# Sensor.net
KiCad netlist of a schematic drawn in Altium Designer
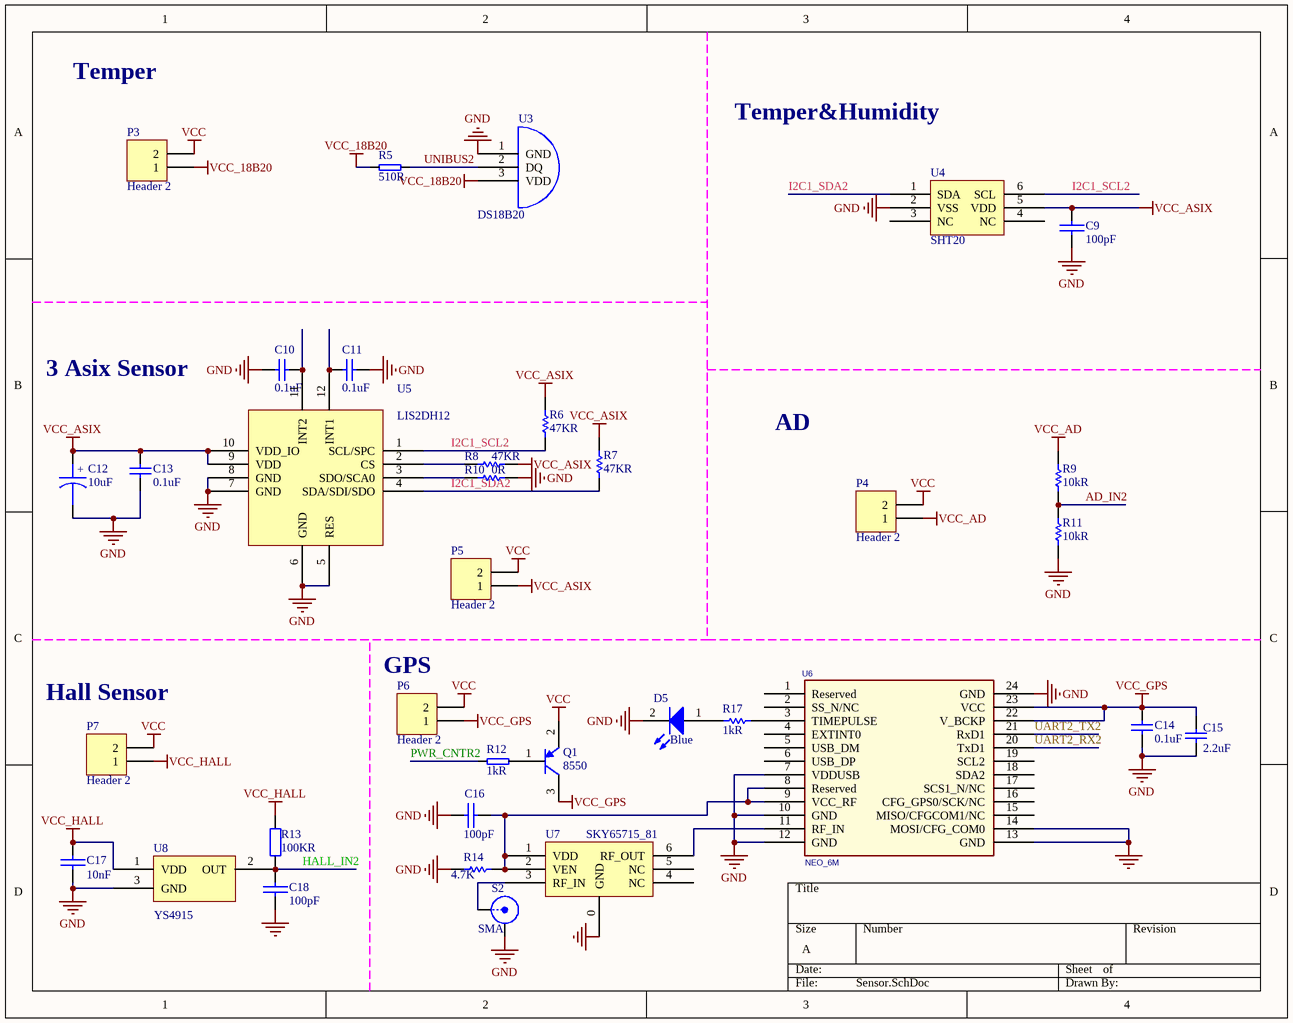
[diagram p0: Sensor.SchDoc]

(export (version "E")
  (design (tool "Eeschema 10.0.6"))
  (components
    (comp (ref "C9")
      (value "100pF")
      (footprint "0603RF")
      (description "Capacitor")
      (libsource (lib "") (part "CAP_1"))
    )
    (comp (ref "C10")
      (value "0.1uF")
      (footprint "0603RF")
      (description "Capacitor (Semiconductor SIM Model)")
      (fields (field (name "PUBLISHER") "Altium Limited"))
      (libsource (lib "Miscellaneous Devices") (part "Cap Semi"))
    )
    (comp (ref "C11")
      (value "0.1uF")
      (footprint "0603RF")
      (description "Capacitor (Semiconductor SIM Model)")
      (fields (field (name "PUBLISHER") "Altium Limited"))
      (libsource (lib "Miscellaneous Devices") (part "Cap Semi"))
    )
    (comp (ref "C12")
      (value "10uF")
      (footprint "0805")
      (description "Capacitor")
      (libsource (lib "*") (part "CAPACITOR POL"))
    )
    (comp (ref "C13")
      (value "0.1uF")
      (footprint "0603RF")
      (description "Capacitor (Semiconductor SIM Model)")
      (fields (field (name "PUBLISHER") "Altium Limited"))
      (libsource (lib "Miscellaneous Devices") (part "Cap Semi"))
    )
    (comp (ref "C14")
      (value "0.1uF")
      (footprint "0603RF")
      (description "Capacitor (Semiconductor SIM Model)")
      (fields (field (name "PUBLISHER") "Altium Limited"))
      (libsource (lib "Miscellaneous Devices") (part "Cap Semi"))
    )
    (comp (ref "C15")
      (value "2.2uF")
      (footprint "0603RF")
      (description "Capacitor (Semiconductor SIM Model)")
      (fields (field (name "PUBLISHER") "Altium Limited"))
      (libsource (lib "Miscellaneous Devices") (part "Cap Semi"))
    )
    (comp (ref "C16")
      (value "100pF")
      (footprint "0603RF")
      (description "Capacitor,100pF/50V,10%,C0603")
      (libsource (lib "Jude") (part "100pF/50V,10%,C0603"))
    )
    (comp (ref "C17")
      (value "10nF")
      (footprint "0603RF")
      (description "Capacitor")
      (libsource (lib "*") (part "CAP"))
    )
    (comp (ref "C18")
      (value "100pF")
      (footprint "0603RF")
      (description "Capacitor")
      (libsource (lib "*") (part "CAP"))
    )
    (comp (ref "D5")
      (value "Blue")
      (footprint "LED0603")
      (description "Typical RED, GREEN, YELLOW, AMBER GaAs LED")
      (fields (field (name "PUBLISHER") "Altium Limited"))
      (libsource (lib "*") (part "LED2"))
    )
    (comp (ref "P3")
      (value "Header 2")
      (footprint "HDR1X2")
      (description "Header, 2-Pin")
      (fields (field (name "PUBLISHER") "Altium Limited"))
      (libsource (lib "Miscellaneous Connectors") (part "Header 2"))
    )
    (comp (ref "P4")
      (value "Header 2")
      (footprint "HDR1X2")
      (description "Header, 2-Pin")
      (fields (field (name "PUBLISHER") "Altium Limited"))
      (libsource (lib "Miscellaneous Connectors") (part "Header 2"))
    )
    (comp (ref "P5")
      (value "Header 2")
      (footprint "HDR1X2")
      (description "Header, 2-Pin")
      (fields (field (name "PUBLISHER") "Altium Limited"))
      (libsource (lib "Miscellaneous Connectors") (part "Header 2"))
    )
    (comp (ref "P6")
      (value "Header 2")
      (footprint "HDR1X2")
      (description "Header, 2-Pin")
      (fields (field (name "PUBLISHER") "Altium Limited"))
      (libsource (lib "Miscellaneous Connectors") (part "Header 2"))
    )
    (comp (ref "P7")
      (value "Header 2")
      (footprint "HDR1X2")
      (description "Header, 2-Pin")
      (fields (field (name "PUBLISHER") "Altium Limited"))
      (libsource (lib "Miscellaneous Connectors") (part "Header 2"))
    )
    (comp (ref "Q1")
      (value "8550")
      (footprint "SO-G3/Z3.3")
      (description "PNP三极管")
      (libsource (lib "MySCHLIB") (part "8550"))
    )
    (comp (ref "R5") (value "510R") (footprint "0603RF") (libsource (lib "*") (part "R")))
    (comp (ref "R6")
      (value "47KR")
      (footprint "0603RF")
      (description "Semiconductor Resistor")
      (fields (field (name "PUBLISHER") "Altium Limited"))
      (libsource (lib "Miscellaneous Devices") (part "Res Semi"))
    )
    (comp (ref "R7")
      (value "47KR")
      (footprint "0603RF")
      (description "Semiconductor Resistor")
      (fields (field (name "PUBLISHER") "Altium Limited"))
      (libsource (lib "Miscellaneous Devices") (part "Res Semi"))
    )
    (comp (ref "R8")
      (value "47KR")
      (footprint "0603RF")
      (description "Semiconductor Resistor")
      (fields (field (name "PUBLISHER") "Altium Limited"))
      (libsource (lib "Miscellaneous Devices") (part "Res Semi"))
    )
    (comp (ref "R9")
      (value "10kR")
      (footprint "0603RF")
      (description "Semiconductor Resistor")
      (fields (field (name "PUBLISHER") "Altium Limited"))
      (libsource (lib "Miscellaneous Devices") (part "Res Semi"))
    )
    (comp (ref "R10")
      (value "0R")
      (footprint "0603RF")
      (description "Semiconductor Resistor")
      (fields (field (name "PUBLISHER") "Altium Limited"))
      (libsource (lib "Miscellaneous Devices") (part "Res Semi"))
    )
    (comp (ref "R11")
      (value "10kR")
      (footprint "0603RF")
      (description "Semiconductor Resistor")
      (fields (field (name "PUBLISHER") "Altium Limited"))
      (libsource (lib "Miscellaneous Devices") (part "Res Semi"))
    )
    (comp (ref "R12") (value "1kR") (footprint "0603RF") (libsource (lib "*") (part "R")))
    (comp (ref "R13")
      (value "100KR")
      (footprint "0603RF")
      (description "Resistor")
      (fields (field (name "PUBLISHER") "Altium Limited"))
      (libsource (lib "Miscellaneous Devices") (part "Res2"))
    )
    (comp (ref "R14") (value "4.7K") (footprint "0603RF") (libsource (lib "Jude") (part "0R,5%,R1206")))
    (comp (ref "R17")
      (value "1kR")
      (footprint "0603RF")
      (description "Semiconductor Resistor")
      (fields (field (name "PUBLISHER") "Altium Limited"))
      (libsource (lib "Miscellaneous Devices") (part "Res Semi"))
    )
    (comp (ref "S2")
      (value "SMA")
      (footprint "SMA")
      (description "SMB Straight Connector")
      (fields (field (name "PUBLISHER") "Altium Limited"))
      (libsource (lib "Miscellaneous Connectors") (part "SMB"))
    )
    (comp (ref "U3")
      (value "DS18B20")
      (footprint "LC-TO-92(TO-92-3)")
      (libsource (lib "MySCHLIB") (part "DS18B20"))
    )
    (comp (ref "U4") (value "SHT20") (footprint "QFN6") (libsource (lib "MySCHLIB") (part "SHT20")))
    (comp (ref "U5") (value "LIS2DH12") (footprint "LIS2DH12") (libsource (lib "MySCHLIB") (part "LIS2DH12")))
    (comp (ref "U6") (value "NEO_6M") (description "GPS模块") (libsource (lib "*") (part "NEO_0")))
    (comp (ref "U7")
      (value "SKY65715_81")
      (footprint "SKY65715")
      (libsource (lib "MySCHLIB") (part "SKY65715"))
    )
    (comp (ref "U8") (value "YS4915") (footprint "SOT-23") (libsource (lib "MySCHLIB") (part "ES248L")))
  )
  (nets
    (net (code "1") (name "/AD_IN2") (class "Default")
      (node (ref "R11") (pin "1") (pinfunction "1_1") (pintype "passive"))
      (node (ref "R9") (pin "2") (pinfunction "2_2") (pintype "passive"))
    )
    (net (code "2") (name "/HALL_IN2") (class "Default")
      (node (ref "C18") (pin "2") (pinfunction "2_2") (pintype "passive"))
      (node (ref "R13") (pin "2") (pinfunction "2_2") (pintype "passive"))
      (node (ref "U8") (pin "2") (pinfunction "OUT_2") (pintype "passive"))
    )
    (net (code "3") (name "/I2C1_SCL2") (class "Default")
      (node (ref "R6") (pin "1") (pinfunction "1_1") (pintype "passive"))
      (node (ref "U4") (pin "6") (pinfunction "SCL_6") (pintype "passive"))
      (node (ref "U5") (pin "1") (pinfunction "SCL/SPC_1") (pintype "passive"))
    )
    (net (code "4") (name "/I2C1_SDA2") (class "Default")
      (node (ref "R7") (pin "1") (pinfunction "1_1") (pintype "passive"))
      (node (ref "U4") (pin "1") (pinfunction "SDA_1") (pintype "passive"))
      (node (ref "U5") (pin "4") (pinfunction "SDA/SDI/SDO_4") (pintype "passive"))
    )
    (net (code "5") (name "/PWR_CNTR2") (class "Default")
      (node (ref "R12") (pin "2") (pinfunction "2_2") (pintype "passive"))
    )
    (net (code "6") (name "/UART2_RX2") (class "Default")
      (node (ref "U6") (pin "20") (pinfunction "TxD1_20") (pintype "passive"))
    )
    (net (code "7") (name "/UART2_TX2") (class "Default")
      (node (ref "U6") (pin "21") (pinfunction "RxD1_21") (pintype "passive"))
    )
    (net (code "8") (name "/UNIBUS2") (class "Default")
      (node (ref "R5") (pin "2") (pinfunction "2_2") (pintype "passive"))
      (node (ref "U3") (pin "2") (pinfunction "DQ_2") (pintype "passive"))
    )
    (net (code "9") (name "GND") (class "Default")
      (node (ref "C10") (pin "2") (pinfunction "2_2") (pintype "passive"))
      (node (ref "C11") (pin "1") (pinfunction "1_1") (pintype "passive"))
      (node (ref "C12") (pin "2") (pinfunction "2_2") (pintype "passive"))
      (node (ref "C13") (pin "1") (pinfunction "1_1") (pintype "passive"))
      (node (ref "C14") (pin "1") (pinfunction "1_1") (pintype "passive"))
      (node (ref "C15") (pin "2") (pinfunction "2_2") (pintype "passive"))
      (node (ref "C16") (pin "1") (pinfunction "1_1") (pintype "passive"))
      (node (ref "C17") (pin "1") (pinfunction "1_1") (pintype "passive"))
      (node (ref "C18") (pin "1") (pinfunction "1_1") (pintype "passive"))
      (node (ref "C9") (pin "1") (pinfunction "1_1") (pintype "passive"))
      (node (ref "D5") (pin "2") (pinfunction "K_2") (pintype "passive"))
      (node (ref "R10") (pin "2") (pinfunction "2_2") (pintype "passive"))
      (node (ref "R11") (pin "2") (pinfunction "2_2") (pintype "passive"))
      (node (ref "R14") (pin "2") (pinfunction "2_2") (pintype "passive"))
      (node (ref "S2") (pin "2") (pinfunction "Y_2") (pintype "passive"))
      (node (ref "U3") (pin "1") (pinfunction "GND_1") (pintype "passive"))
      (node (ref "U4") (pin "2") (pinfunction "VSS_2") (pintype "passive"))
      (node (ref "U5") (pin "5") (pinfunction "RES_5") (pintype "passive"))
      (node (ref "U5") (pin "6") (pinfunction "GND_6") (pintype "passive"))
      (node (ref "U5") (pin "7") (pinfunction "GND_7") (pintype "passive"))
      (node (ref "U5") (pin "8") (pinfunction "GND_8") (pintype "passive"))
      (node (ref "U6") (pin "10") (pinfunction "GND_10") (pintype "passive"))
      (node (ref "U6") (pin "12") (pinfunction "GND_12") (pintype "passive"))
      (node (ref "U6") (pin "13") (pinfunction "GND_13") (pintype "passive"))
      (node (ref "U6") (pin "14") (pinfunction "MOSI/CFG_COM0_14") (pintype "passive"))
      (node (ref "U6") (pin "24") (pinfunction "GND_24") (pintype "passive"))
      (node (ref "U6") (pin "7") (pinfunction "VDDUSB_7") (pintype "passive"))
      (node (ref "U7") (pin "0") (pinfunction "GND_0") (pintype "passive"))
      (node (ref "U8") (pin "3") (pinfunction "GND_3") (pintype "passive"))
    )
    (net (code "10") (name "Net-(D5-A)") (class "Default")
      (node (ref "D5") (pin "1") (pinfunction "A_1") (pintype "passive"))
      (node (ref "R17") (pin "1") (pinfunction "1_1") (pintype "passive"))
    )
    (net (code "11") (name "Net-(Q1-B)") (class "Default")
      (node (ref "Q1") (pin "1") (pinfunction "B_1") (pintype "passive"))
      (node (ref "R12") (pin "1") (pinfunction "1_1") (pintype "passive"))
    )
    (net (code "12") (name "Net-(S2-X)") (class "Default")
      (node (ref "S2") (pin "1") (pinfunction "X_1") (pintype "passive"))
      (node (ref "U7") (pin "3") (pinfunction "RF_IN_3") (pintype "passive"))
    )
    (net (code "13") (name "Net-(U5-CS)") (class "Default")
      (node (ref "R8") (pin "1") (pinfunction "1_1") (pintype "passive"))
      (node (ref "U5") (pin "2") (pinfunction "CS_2") (pintype "passive"))
    )
    (net (code "14") (name "Net-(U5-INT1)") (class "Default")
      (node (ref "C11") (pin "2") (pinfunction "2_2") (pintype "passive"))
      (node (ref "U5") (pin "12") (pinfunction "INT1_12") (pintype "passive"))
    )
    (net (code "15") (name "Net-(U5-INT2)") (class "Default")
      (node (ref "C10") (pin "1") (pinfunction "1_1") (pintype "passive"))
      (node (ref "U5") (pin "11") (pinfunction "INT2_11") (pintype "passive"))
    )
    (net (code "16") (name "Net-(U5-SDO{slash}SCA0)") (class "Default")
      (node (ref "R10") (pin "1") (pinfunction "1_1") (pintype "passive"))
      (node (ref "U5") (pin "3") (pinfunction "SDO/SCA0_3") (pintype "passive"))
    )
    (net (code "17") (name "Net-(U6-RF_IN)") (class "Default")
      (node (ref "U6") (pin "11") (pinfunction "RF_IN_11") (pintype "passive"))
      (node (ref "U7") (pin "6") (pinfunction "RF_OUT_6") (pintype "passive"))
    )
    (net (code "18") (name "Net-(U6-TIMEPULSE)") (class "Default")
      (node (ref "R17") (pin "2") (pinfunction "2_2") (pintype "passive"))
      (node (ref "U6") (pin "3") (pinfunction "TIMEPULSE_3") (pintype "passive"))
    )
    (net (code "19") (name "Net-(U6-VCC_RF)") (class "Default")
      (node (ref "C16") (pin "2") (pinfunction "2_2") (pintype "passive"))
      (node (ref "R14") (pin "1") (pinfunction "1_1") (pintype "passive"))
      (node (ref "U6") (pin "8") (pinfunction "Reserved_8") (pintype "passive"))
      (node (ref "U6") (pin "9") (pinfunction "VCC_RF_9") (pintype "passive"))
      (node (ref "U7") (pin "1") (pinfunction "VDD_1") (pintype "passive"))
      (node (ref "U7") (pin "2") (pinfunction "VEN_2") (pintype "passive"))
    )
    (net (code "20") (name "VCC") (class "Default")
      (node (ref "P3") (pin "2") (pinfunction "2_2") (pintype "passive"))
      (node (ref "P4") (pin "2") (pinfunction "2_2") (pintype "passive"))
      (node (ref "P5") (pin "2") (pinfunction "2_2") (pintype "passive"))
      (node (ref "P6") (pin "2") (pinfunction "2_2") (pintype "passive"))
      (node (ref "P7") (pin "2") (pinfunction "2_2") (pintype "passive"))
      (node (ref "Q1") (pin "2") (pinfunction "E_2") (pintype "passive"))
    )
    (net (code "21") (name "VCC_18B20") (class "Default")
      (node (ref "P3") (pin "1") (pinfunction "1_1") (pintype "passive"))
      (node (ref "R5") (pin "1") (pinfunction "1_1") (pintype "passive"))
      (node (ref "U3") (pin "3") (pinfunction "VDD_3") (pintype "passive"))
    )
    (net (code "22") (name "VCC_AD") (class "Default")
      (node (ref "P4") (pin "1") (pinfunction "1_1") (pintype "passive"))
      (node (ref "R9") (pin "1") (pinfunction "1_1") (pintype "passive"))
    )
    (net (code "23") (name "VCC_ASIX") (class "Default")
      (node (ref "C12") (pin "1") (pinfunction "1_1") (pintype "passive"))
      (node (ref "C13") (pin "2") (pinfunction "2_2") (pintype "passive"))
      (node (ref "C9") (pin "2") (pinfunction "2_2") (pintype "passive"))
      (node (ref "P5") (pin "1") (pinfunction "1_1") (pintype "passive"))
      (node (ref "R6") (pin "2") (pinfunction "2_2") (pintype "passive"))
      (node (ref "R7") (pin "2") (pinfunction "2_2") (pintype "passive"))
      (node (ref "R8") (pin "2") (pinfunction "2_2") (pintype "passive"))
      (node (ref "U4") (pin "5") (pinfunction "VDD_5") (pintype "passive"))
      (node (ref "U5") (pin "10") (pinfunction "VDD_IO_10") (pintype "passive"))
      (node (ref "U5") (pin "9") (pinfunction "VDD_9") (pintype "passive"))
    )
    (net (code "24") (name "VCC_GPS") (class "Default")
      (node (ref "C14") (pin "2") (pinfunction "2_2") (pintype "passive"))
      (node (ref "C15") (pin "1") (pinfunction "1_1") (pintype "passive"))
      (node (ref "P6") (pin "1") (pinfunction "1_1") (pintype "passive"))
      (node (ref "Q1") (pin "3") (pinfunction "C_3") (pintype "passive"))
      (node (ref "U6") (pin "22") (pinfunction "V_BCKP_22") (pintype "passive"))
      (node (ref "U6") (pin "23") (pinfunction "VCC_23") (pintype "passive"))
    )
    (net (code "25") (name "VCC_HALL") (class "Default")
      (node (ref "C17") (pin "2") (pinfunction "2_2") (pintype "passive"))
      (node (ref "P7") (pin "1") (pinfunction "1_1") (pintype "passive"))
      (node (ref "R13") (pin "1") (pinfunction "1_1") (pintype "passive"))
      (node (ref "U8") (pin "1") (pinfunction "VDD_1") (pintype "passive"))
    )
    (net (code "26") (name "unconnected-(U4-NC-Pad3)") (class "Default")
      (node (ref "U4") (pin "3") (pinfunction "NC_3") (pintype "passive"))
    )
    (net (code "27") (name "unconnected-(U4-NC-Pad4)") (class "Default")
      (node (ref "U4") (pin "4") (pinfunction "NC_4") (pintype "passive"))
    )
    (net (code "28") (name "unconnected-(U6-CFG_GPS0{slash}SCK{slash}NC-Pad16)") (class "Default")
      (node (ref "U6") (pin "16") (pinfunction "CFG_GPS0/SCK/NC_16") (pintype "passive"))
    )
    (net (code "29") (name "unconnected-(U6-EXTINT0-Pad4)") (class "Default")
      (node (ref "U6") (pin "4") (pinfunction "EXTINT0_4") (pintype "passive"))
    )
    (net (code "30") (name "unconnected-(U6-MISO{slash}CFGCOM1{slash}NC-Pad15)") (class "Default")
      (node (ref "U6") (pin "15") (pinfunction "MISO/CFGCOM1/NC_15") (pintype "passive"))
    )
    (net (code "31") (name "unconnected-(U6-Reserved-Pad1)") (class "Default")
      (node (ref "U6") (pin "1") (pinfunction "Reserved_1") (pintype "passive"))
    )
    (net (code "32") (name "unconnected-(U6-SCL2-Pad19)") (class "Default")
      (node (ref "U6") (pin "19") (pinfunction "SCL2_19") (pintype "passive"))
    )
    (net (code "33") (name "unconnected-(U6-SCS1_N{slash}NC-Pad17)") (class "Default")
      (node (ref "U6") (pin "17") (pinfunction "SCS1_N/NC_17") (pintype "passive"))
    )
    (net (code "34") (name "unconnected-(U6-SDA2-Pad18)") (class "Default")
      (node (ref "U6") (pin "18") (pinfunction "SDA2_18") (pintype "passive"))
    )
    (net (code "35") (name "unconnected-(U6-SS_N{slash}NC-Pad2)") (class "Default")
      (node (ref "U6") (pin "2") (pinfunction "SS_N/NC_2") (pintype "passive"))
    )
    (net (code "36") (name "unconnected-(U6-USB_DM-Pad5)") (class "Default")
      (node (ref "U6") (pin "5") (pinfunction "USB_DM_5") (pintype "passive"))
    )
    (net (code "37") (name "unconnected-(U6-USB_DP-Pad6)") (class "Default")
      (node (ref "U6") (pin "6") (pinfunction "USB_DP_6") (pintype "passive"))
    )
    (net (code "38") (name "unconnected-(U7-NC-Pad4)") (class "Default")
      (node (ref "U7") (pin "4") (pinfunction "NC_4") (pintype "passive"))
    )
    (net (code "39") (name "unconnected-(U7-NC-Pad5)") (class "Default")
      (node (ref "U7") (pin "5") (pinfunction "NC_5") (pintype "passive"))
    )
  )
)
